# ESP32C_RF.net
KiCad netlist of a schematic drawn in Altium Designer
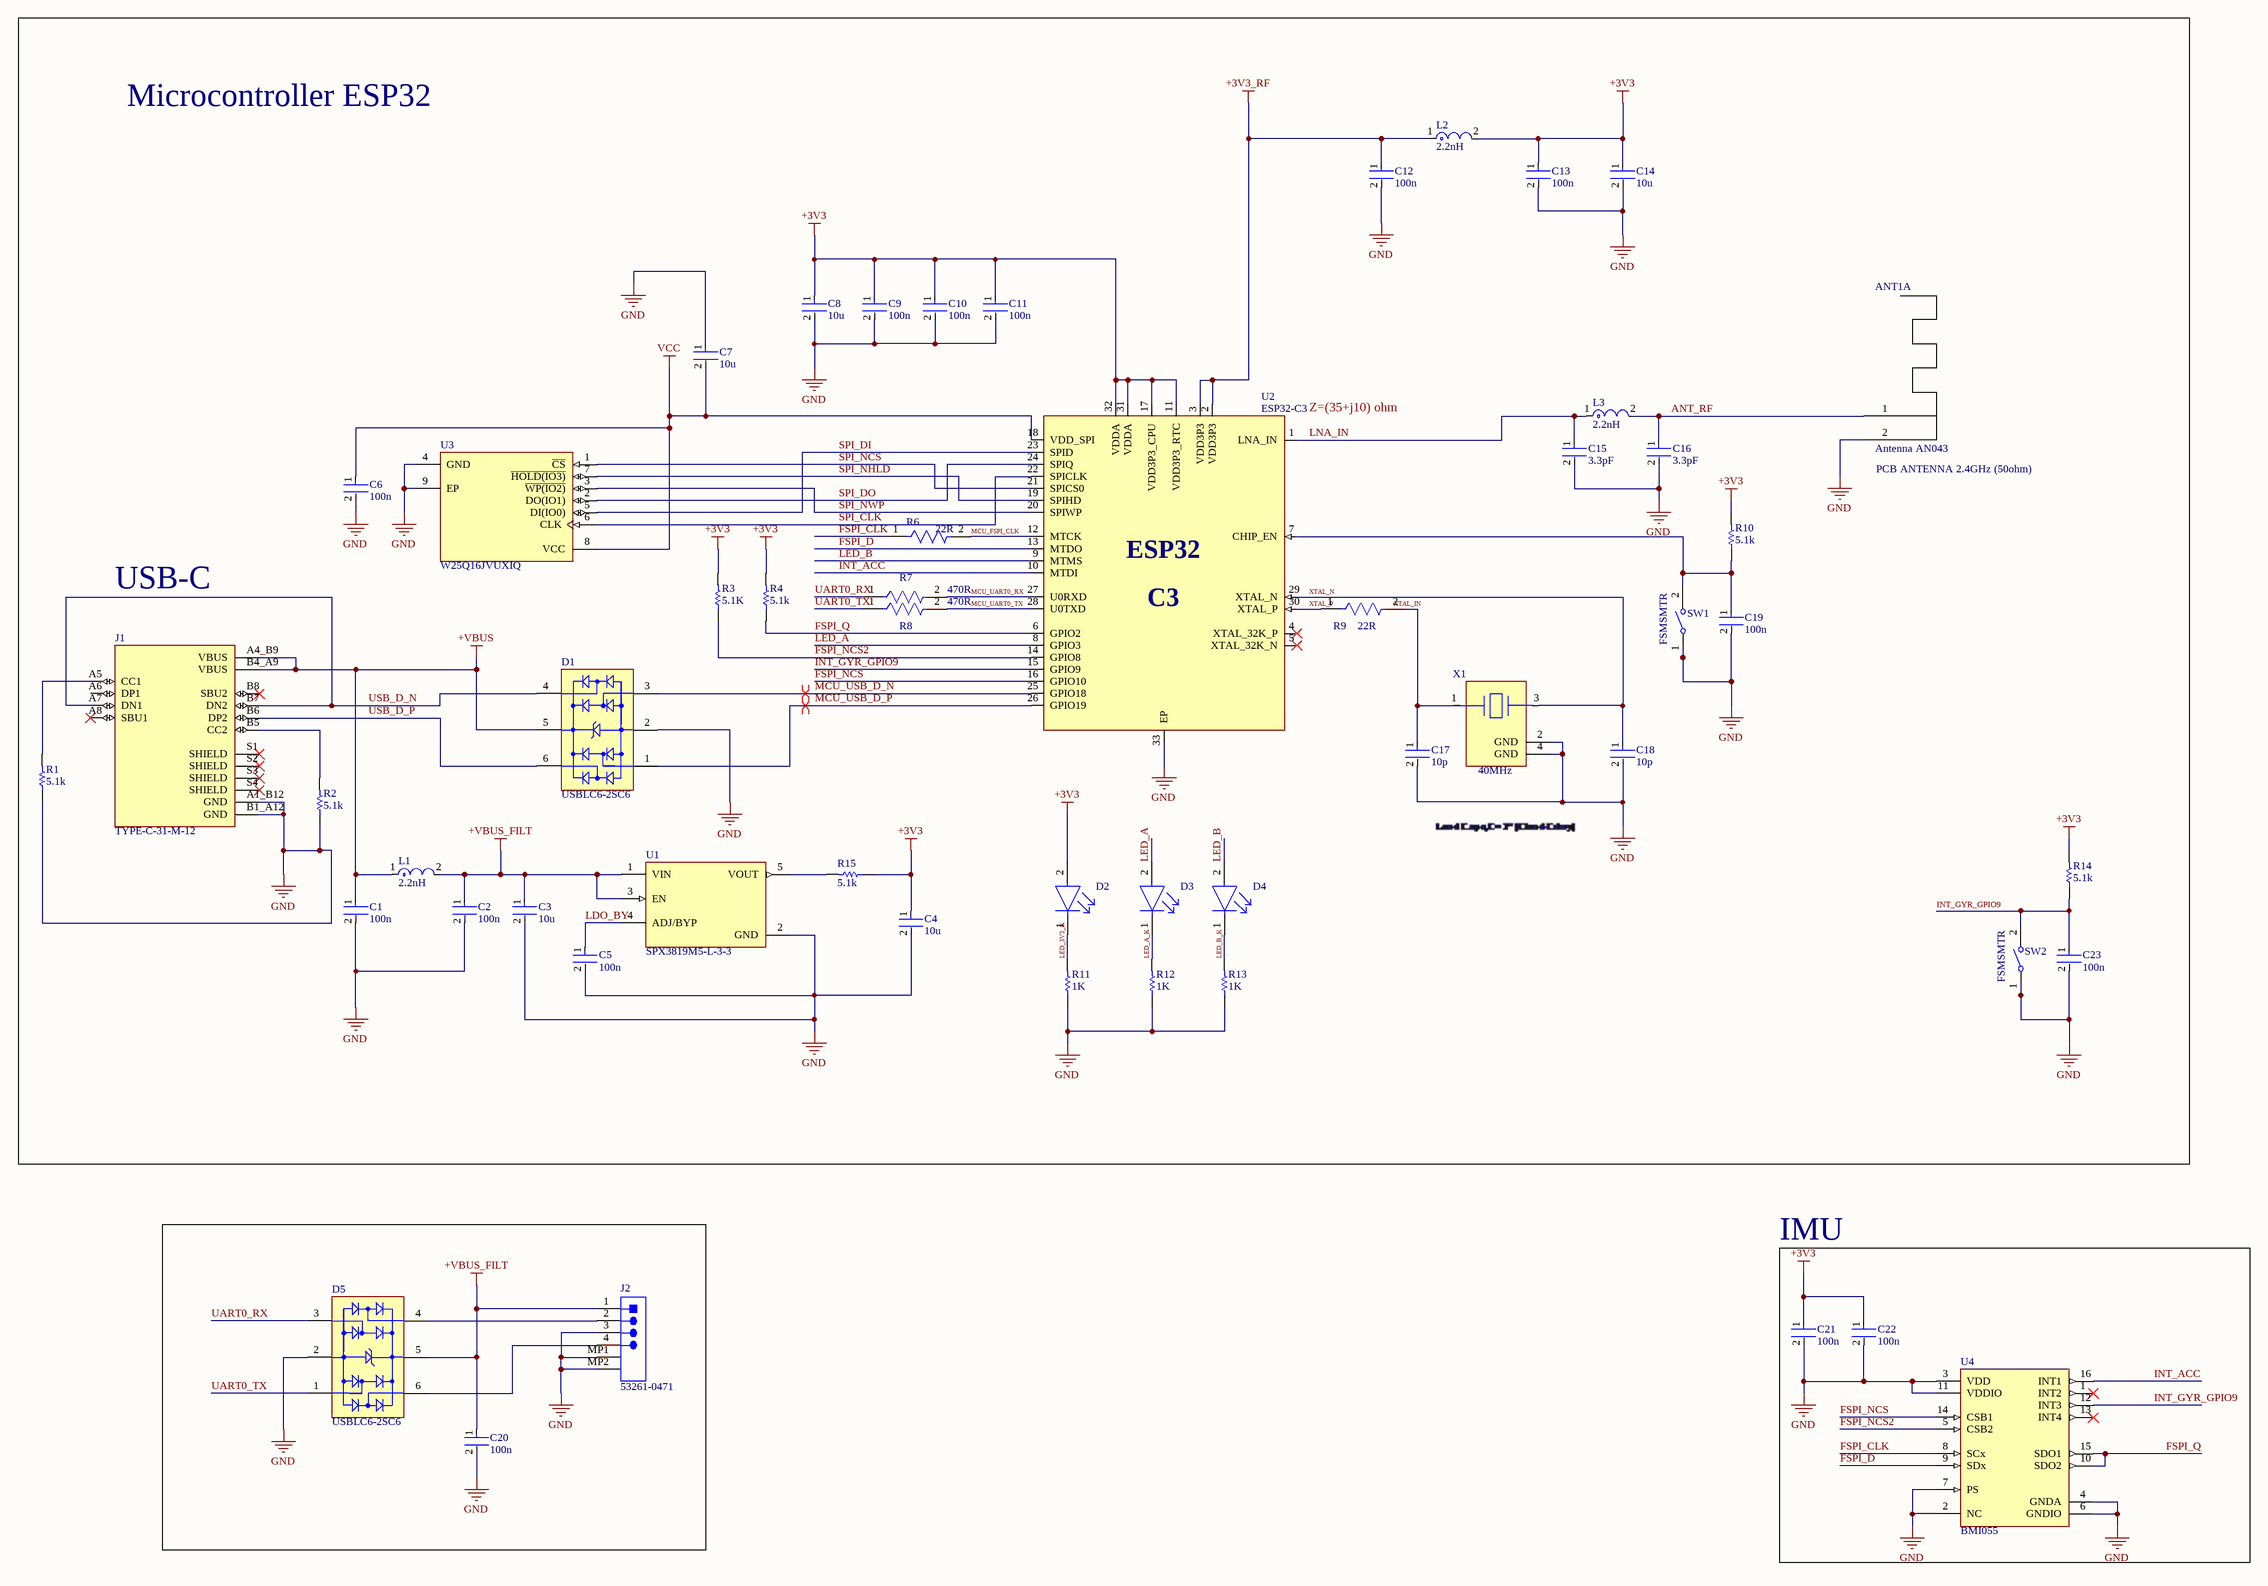
[diagram p0: ESP32C_RF.SchDoc]

(export (version "E")
  (design (tool "Eeschema 10.0.6"))
  (components
    (comp (ref "ANT1")
      (value "Antenna AN043")
      (footprint "Antenna_AN043")
      (libsource (lib "Library_Esp32C") (part "Antenna AN043"))
    )
    (comp (ref "C1")
      (value "100n")
      (footprint "FP-C0402-BB-MFG")
      (description "CAP CER 0.1UF 10V X5R 0402")
      (fields (field (name "MANUFACTURER") "Kemet") (field (name "TOLERANCE") "0.1"))
      (libsource (lib "Altium Content Vault") (part "b4654b650e69147ec39a6b967a45e02"))
    )
    (comp (ref "C2")
      (value "100n")
      (footprint "FP-C0402-BB-MFG")
      (description "CAP CER 0.1UF 10V X5R 0402")
      (fields (field (name "MANUFACTURER") "Kemet") (field (name "TOLERANCE") "0.1"))
      (libsource (lib "Altium Content Vault") (part "b4654b650e69147ec39a6b967a45e02"))
    )
    (comp (ref "C3")
      (value "10u")
      (footprint "FP-0603-L_1_6_0_15-W_0_81-MFG")
      (description "General Purpose Ceramic Capacitor, 0603, 100nF, 10%, X7R, 15%, 50V")
      (fields (field (name "TOLERANCE") "10%") (field (name "VOLTAGE") "50V"))
      (libsource (lib "Altium Content Vault") (part "02cd4be3c70576c341d710602a673aa"))
    )
    (comp (ref "C4")
      (value "10u")
      (footprint "FP-0603-L_1_6_0_15-W_0_81-MFG")
      (description "General Purpose Ceramic Capacitor, 0603, 100nF, 10%, X7R, 15%, 50V")
      (fields (field (name "TOLERANCE") "10%") (field (name "VOLTAGE") "50V"))
      (libsource (lib "Altium Content Vault") (part "02cd4be3c70576c341d710602a673aa"))
    )
    (comp (ref "C5")
      (value "100n")
      (footprint "FP-C0402-BB-MFG")
      (description "CAP CER 0.1UF 10V X5R 0402")
      (fields (field (name "MANUFACTURER") "Kemet") (field (name "TOLERANCE") "0.1"))
      (libsource (lib "Altium Content Vault") (part "b4654b650e69147ec39a6b967a45e02"))
    )
    (comp (ref "C6")
      (value "100n")
      (footprint "FP-C0402-BB-MFG")
      (description "CAP CER 0.1UF 10V X5R 0402")
      (fields (field (name "MANUFACTURER") "Kemet") (field (name "TOLERANCE") "0.1"))
      (libsource (lib "Altium Content Vault") (part "b4654b650e69147ec39a6b967a45e02"))
    )
    (comp (ref "C7")
      (value "10u")
      (footprint "FP-0603-L_1_6_0_15-W_0_81-MFG")
      (description "General Purpose Ceramic Capacitor, 0603, 100nF, 10%, X7R, 15%, 50V")
      (fields (field (name "TOLERANCE") "10%") (field (name "VOLTAGE") "50V"))
      (libsource (lib "Altium Content Vault") (part "02cd4be3c70576c341d710602a673aa"))
    )
    (comp (ref "C8")
      (value "10u")
      (footprint "FP-0603-L_1_6_0_15-W_0_81-MFG")
      (description "General Purpose Ceramic Capacitor, 0603, 100nF, 10%, X7R, 15%, 50V")
      (fields (field (name "TOLERANCE") "10%") (field (name "VOLTAGE") "50V"))
      (libsource (lib "Altium Content Vault") (part "02cd4be3c70576c341d710602a673aa"))
    )
    (comp (ref "C9")
      (value "100n")
      (footprint "FP-C0402-BB-MFG")
      (description "CAP CER 0.1UF 10V X5R 0402")
      (fields (field (name "MANUFACTURER") "Kemet") (field (name "TOLERANCE") "0.1"))
      (libsource (lib "Altium Content Vault") (part "b4654b650e69147ec39a6b967a45e02"))
    )
    (comp (ref "C10")
      (value "100n")
      (footprint "FP-C0402-BB-MFG")
      (description "CAP CER 0.1UF 10V X5R 0402")
      (fields (field (name "MANUFACTURER") "Kemet") (field (name "TOLERANCE") "0.1"))
      (libsource (lib "Altium Content Vault") (part "b4654b650e69147ec39a6b967a45e02"))
    )
    (comp (ref "C11")
      (value "100n")
      (footprint "FP-C0402-BB-MFG")
      (description "CAP CER 0.1UF 10V X5R 0402")
      (fields (field (name "MANUFACTURER") "Kemet") (field (name "TOLERANCE") "0.1"))
      (libsource (lib "Altium Content Vault") (part "b4654b650e69147ec39a6b967a45e02"))
    )
    (comp (ref "C12")
      (value "100n")
      (footprint "FP-C0402-BB-MFG")
      (description "CAP CER 0.1UF 10V X5R 0402")
      (fields (field (name "MANUFACTURER") "Kemet") (field (name "TOLERANCE") "0.1"))
      (libsource (lib "Altium Content Vault") (part "b4654b650e69147ec39a6b967a45e02"))
    )
    (comp (ref "C13")
      (value "100n")
      (footprint "FP-C0402-BB-MFG")
      (description "CAP CER 0.1UF 10V X5R 0402")
      (fields (field (name "MANUFACTURER") "Kemet") (field (name "TOLERANCE") "0.1"))
      (libsource (lib "Altium Content Vault") (part "b4654b650e69147ec39a6b967a45e02"))
    )
    (comp (ref "C14")
      (value "10u")
      (footprint "FP-0603-L_1_6_0_15-W_0_81-MFG")
      (description "General Purpose Ceramic Capacitor, 0603, 100nF, 10%, X7R, 15%, 50V")
      (fields (field (name "TOLERANCE") "10%") (field (name "VOLTAGE") "50V"))
      (libsource (lib "Altium Content Vault") (part "02cd4be3c70576c341d710602a673aa"))
    )
    (comp (ref "C15")
      (value "3.3pF")
      (footprint "FP-C0402-BB-MFG")
      (description "CAP CER 0.1UF 10V X5R 0402")
      (fields (field (name "MANUFACTURER") "Kemet") (field (name "TOLERANCE") "0.1"))
      (libsource (lib "Altium Content Vault") (part "b4654b650e69147ec39a6b967a45e02"))
    )
    (comp (ref "C16")
      (value "3.3pF")
      (footprint "FP-C0402-BB-MFG")
      (description "CAP CER 0.1UF 10V X5R 0402")
      (fields (field (name "MANUFACTURER") "Kemet") (field (name "TOLERANCE") "0.1"))
      (libsource (lib "Altium Content Vault") (part "b4654b650e69147ec39a6b967a45e02"))
    )
    (comp (ref "C17")
      (value "10p")
      (footprint "FP-C0402-BB-MFG")
      (description "CAP CER 0.1UF 10V X5R 0402")
      (fields (field (name "MANUFACTURER") "Kemet") (field (name "TOLERANCE") "0.1"))
      (libsource (lib "Altium Content Vault") (part "b4654b650e69147ec39a6b967a45e02"))
    )
    (comp (ref "C18")
      (value "10p")
      (footprint "FP-C0402-BB-MFG")
      (description "CAP CER 0.1UF 10V X5R 0402")
      (fields (field (name "MANUFACTURER") "Kemet") (field (name "TOLERANCE") "0.1"))
      (libsource (lib "Altium Content Vault") (part "b4654b650e69147ec39a6b967a45e02"))
    )
    (comp (ref "C19")
      (value "100n")
      (footprint "FP-C0402-BB-MFG")
      (description "CAP CER 0.1UF 10V X5R 0402")
      (fields (field (name "MANUFACTURER") "Kemet") (field (name "TOLERANCE") "0.1"))
      (libsource (lib "Altium Content Vault") (part "b4654b650e69147ec39a6b967a45e02"))
    )
    (comp (ref "C20")
      (value "100n")
      (footprint "FP-C0402-BB-MFG")
      (description "CAP CER 0.1UF 10V X5R 0402")
      (fields (field (name "MANUFACTURER") "Kemet") (field (name "TOLERANCE") "0.1"))
      (libsource (lib "Altium Content Vault") (part "b4654b650e69147ec39a6b967a45e02"))
    )
    (comp (ref "C21")
      (value "100n")
      (footprint "FP-C0402-BB-MFG")
      (description "CAP CER 0.1UF 10V X5R 0402")
      (fields (field (name "MANUFACTURER") "Kemet") (field (name "TOLERANCE") "0.1"))
      (libsource (lib "Altium Content Vault") (part "b4654b650e69147ec39a6b967a45e02"))
    )
    (comp (ref "C22")
      (value "100n")
      (footprint "FP-C0402-BB-MFG")
      (description "CAP CER 0.1UF 10V X5R 0402")
      (fields (field (name "MANUFACTURER") "Kemet") (field (name "TOLERANCE") "0.1"))
      (libsource (lib "Altium Content Vault") (part "b4654b650e69147ec39a6b967a45e02"))
    )
    (comp (ref "C23")
      (value "100n")
      (footprint "FP-C0402-BB-MFG")
      (description "CAP CER 0.1UF 10V X5R 0402")
      (fields (field (name "MANUFACTURER") "Kemet") (field (name "TOLERANCE") "0.1"))
      (libsource (lib "Altium Content Vault") (part "b4654b650e69147ec39a6b967a45e02"))
    )
    (comp (ref "D1")
      (value "USBLC6-2SC6")
      (footprint "STM-SOT23-6L_V")
      (description "Very low capacitance ESD protection, 3.5 pF, -40 to 125 degC, 6-Pin SOT23, RoHS, Tape and Reel")
      (fields (field (name "MANUFACTURER") "STMicroelectronics"))
      (libsource (lib "Altium Content Vault") (part "STM-USB_DVI_HDMIULC6-4SC6X-SOT23-6L"))
    )
    (comp (ref "D2")
      (value "LTST-C190KRKT")
      (footprint "FP-LTST-C190KRKT-MFG")
      (description "LED RED CLEAR CHIP SMD")
      (libsource (lib "Altium Content Vault") (part "8706943c75ba83719d021d2fdc84c58"))
    )
    (comp (ref "D3")
      (value "LTST-C190KRKT")
      (footprint "FP-LTST-C190KRKT-MFG")
      (description "LED RED CLEAR CHIP SMD")
      (libsource (lib "Altium Content Vault") (part "8706943c75ba83719d021d2fdc84c58"))
    )
    (comp (ref "D4")
      (value "LTST-C190KRKT")
      (footprint "FP-LTST-C190KRKT-MFG")
      (description "LED RED CLEAR CHIP SMD")
      (libsource (lib "Altium Content Vault") (part "8706943c75ba83719d021d2fdc84c58"))
    )
    (comp (ref "D5")
      (value "USBLC6-2SC6")
      (footprint "STM-SOT23-6L_V")
      (description "Very low capacitance ESD protection, 3.5 pF, -40 to 125 degC, 6-Pin SOT23, RoHS, Tape and Reel")
      (fields (field (name "MANUFACTURER") "STMicroelectronics"))
      (libsource (lib "Altium Content Vault") (part "STM-USB_DVI_HDMIULC6-4SC6X-SOT23-6L"))
    )
    (comp (ref "J1")
      (value "TYPE-C-31-M-12")
      (footprint "HRO_TYPE-C-31-M-12")
      (description "USB Connectors 24 Receptacle 1 8.94*7.3mm RoHS")
      (fields (field (name "MF") "HRO Electronics Co., Ltd."))
      (libsource (lib "Library_Esp32C") (part "TYPE-C-31-M-12"))
    )
    (comp (ref "J2")
      (value "53261-0471")
      (footprint "MOLEX-53261-0471_V")
      (description "Male Header, Pitch 1.25 mm, 1 x 4 Position, Height 3.4 mm, -40 to 85 degC, RoHS, Tape and Reel")
      (fields (field (name "MANUFACTURER") "Molex"))
      (libsource (lib "Altium Content Vault") (part "CN-1P-2M-R4_A"))
    )
    (comp (ref "L1")
      (value "2.2nH")
      (footprint "FP-LQG15HH_02-IPC_A")
      (description "Multilayer type RF Inductor 3.6nH ±0.3nH 0.13Ω 700mA 0402")
      (libsource (lib "Altium Content Vault") (part "4cc4b267dca4c8e51f7102f422741d8"))
    )
    (comp (ref "L2")
      (value "2.2nH")
      (footprint "FP-LQG15HH_02-IPC_A")
      (description "Multilayer type RF Inductor 3.6nH ±0.3nH 0.13Ω 700mA 0402")
      (libsource (lib "Altium Content Vault") (part "4cc4b267dca4c8e51f7102f422741d8"))
    )
    (comp (ref "L3")
      (value "2.2nH")
      (footprint "FP-LQG15HH_02-IPC_A")
      (description "Multilayer type RF Inductor 3.6nH ±0.3nH 0.13Ω 700mA 0402")
      (libsource (lib "Altium Content Vault") (part "4cc4b267dca4c8e51f7102f422741d8"))
    )
    (comp (ref "R1")
      (value "5.1k")
      (footprint "RESC1005X40X25LL05T05")
      (fields (field (name "MANUFACTURER") "Vishay Dale") (field (name "PART NUMBER") "CRCW040222R0FKED"))
      (libsource (lib "Altium Content Vault") (part "RES"))
    )
    (comp (ref "R2")
      (value "5.1k")
      (footprint "RESC1005X40X25LL05T05")
      (fields (field (name "MANUFACTURER") "Vishay Dale") (field (name "PART NUMBER") "CRCW040222R0FKED"))
      (libsource (lib "Altium Content Vault") (part "RES"))
    )
    (comp (ref "R3")
      (value "5.1K")
      (footprint "RESC1005X40X25LL05T05")
      (fields (field (name "MANUFACTURER") "Vishay Dale") (field (name "PART NUMBER") "CRCW040222R0FKED"))
      (libsource (lib "Altium Content Vault") (part "RES"))
    )
    (comp (ref "R4")
      (value "5.1k")
      (footprint "RESC1005X40X25LL05T05")
      (fields (field (name "MANUFACTURER") "Vishay Dale") (field (name "PART NUMBER") "CRCW040222R0FKED"))
      (libsource (lib "Altium Content Vault") (part "RES"))
    )
    (comp (ref "R6")
      (value "22R")
      (footprint "FP-CRCW0402-e3-IPC_C")
      (description "RES Thick Film, 100Ω, 1%, 0.063W, 100ppm/°C, 0402")
      (fields (field (name "TOLERANCE") "1%"))
      (libsource (lib "Altium Content Vault") (part "1029c3af85768c4190bb7ad29bc67b5"))
    )
    (comp (ref "R7")
      (value "470R")
      (footprint "FP-ERJ2RK-IPC_C")
      (description "RES SMD 470 OHM 1% 1/10W 0402")
      (fields (field (name "TOLERANCE") "1%"))
      (libsource (lib "Altium Content Vault") (part "8db39607336c341a927600551d01821"))
    )
    (comp (ref "R8")
      (value "470R")
      (footprint "FP-ERJ2RK-IPC_C")
      (description "RES SMD 470 OHM 1% 1/10W 0402")
      (fields (field (name "TOLERANCE") "1%"))
      (libsource (lib "Altium Content Vault") (part "8db39607336c341a927600551d01821"))
    )
    (comp (ref "R9")
      (value "22R")
      (footprint "FP-CRCW0402-e3-IPC_C")
      (description "RES Thick Film, 100Ω, 1%, 0.063W, 100ppm/°C, 0402")
      (fields (field (name "TOLERANCE") "1%"))
      (libsource (lib "Altium Content Vault") (part "1029c3af85768c4190bb7ad29bc67b5"))
    )
    (comp (ref "R10")
      (value "5.1k")
      (footprint "RESC1005X40X25LL05T05")
      (fields (field (name "MANUFACTURER") "Vishay Dale") (field (name "PART NUMBER") "CRCW040222R0FKED"))
      (libsource (lib "Altium Content Vault") (part "RES"))
    )
    (comp (ref "R11")
      (value "1K")
      (footprint "RESC1005X40X25LL05T05")
      (fields (field (name "MANUFACTURER") "Vishay Dale") (field (name "PART NUMBER") "CRCW040222R0FKED"))
      (libsource (lib "Altium Content Vault") (part "RES"))
    )
    (comp (ref "R12")
      (value "1K")
      (footprint "RESC1005X40X25LL05T05")
      (fields (field (name "MANUFACTURER") "Vishay Dale") (field (name "PART NUMBER") "CRCW040222R0FKED"))
      (libsource (lib "Altium Content Vault") (part "RES"))
    )
    (comp (ref "R13")
      (value "1K")
      (footprint "RESC1005X40X25LL05T05")
      (fields (field (name "MANUFACTURER") "Vishay Dale") (field (name "PART NUMBER") "CRCW040222R0FKED"))
      (libsource (lib "Altium Content Vault") (part "RES"))
    )
    (comp (ref "R14")
      (value "5.1k")
      (footprint "RESC1005X40X25LL05T05")
      (fields (field (name "MANUFACTURER") "Vishay Dale") (field (name "PART NUMBER") "CRCW040222R0FKED"))
      (libsource (lib "Altium Content Vault") (part "RES"))
    )
    (comp (ref "R15")
      (value "5.1k")
      (footprint "RESC1005X40X25LL05T05")
      (fields (field (name "MANUFACTURER") "Vishay Dale") (field (name "PART NUMBER") "CRCW040222R0FKED"))
      (libsource (lib "Altium Content Vault") (part "RES"))
    )
    (comp (ref "SW1")
      (value "FSMSMTR")
      (footprint "TECO-FSMSMTR_V")
      (description "FSMSM Push Button Switch, 50 mA, -35 to 85 degC, 2-Pin SMD, RoHS, Tape and Reel")
      (fields (field (name "MANUFACTURER") "TE Connectivity"))
      (libsource (lib "Altium Content Vault") (part "SW-SPST-2_C"))
    )
    (comp (ref "SW2")
      (value "FSMSMTR")
      (footprint "TECO-FSMSMTR_V")
      (description "FSMSM Push Button Switch, 50 mA, -35 to 85 degC, 2-Pin SMD, RoHS, Tape and Reel")
      (fields (field (name "MANUFACTURER") "TE Connectivity"))
      (libsource (lib "Altium Content Vault") (part "SW-SPST-2_C"))
    )
    (comp (ref "U1")
      (value "SPX3819M5-L-3-3")
      (footprint "SOT95P280X145-5N")
      (description "Linear Voltage Regulator IC Positive Fixed 1 Output 500mA SOT-23-5")
      (fields (field (name "MF") "MaxLinear, Inc.") (field (name "MP") "SPX3819M5-L-3-3/TR"))
      (libsource (lib "Library_Esp32C") (part "SPX3819M5-L-3-3"))
    )
    (comp (ref "U2")
      (value "ESP32-C3")
      (footprint "QFN50P500X500X90-33N-D")
      (fields (field (name "MANUFACTURER") "Espressif"))
      (libsource (lib "Library_Esp32C") (part "ESP32-C3"))
    )
    (comp (ref "U3")
      (value "W25Q16JVUXIQ")
      (footprint "FP-UX-MFG")
      (description "IC FLASH 16MBIT SPI/QUAD 8USON")
      (libsource (lib "Altium Content Vault") (part "ef7e6bbff5b18f94b0c5acc221a373e"))
    )
    (comp (ref "U4")
      (value "BMI055")
      (footprint "FP-BMI055-MFG")
      (description "IMU ACCEL/GYRO I2C/SPI 16LGA")
      (libsource (lib "Altium Content Vault") (part "27928433b13d6d742e94b461c0d61b2"))
    )
    (comp (ref "X1")
      (value "40MHz")
      (footprint "FP-NX2520SA-MFG")
      (description "CRYSTAL 16.0000MHZ 8PF SMD")
      (libsource (lib "Altium Content Vault") (part "07cd68334262f73c450eeb7a763f26b"))
    )
  )
  (nets
    (net (code "1") (name "+3V3") (class "Default")
      (node (ref "C10") (pin "1") (pinfunction "1_1") (pintype "passive"))
      (node (ref "C11") (pin "1") (pinfunction "1_1") (pintype "passive"))
      (node (ref "C13") (pin "1") (pinfunction "1_1") (pintype "passive"))
      (node (ref "C14") (pin "1") (pinfunction "1_1") (pintype "passive"))
      (node (ref "C21") (pin "1") (pinfunction "1_1") (pintype "passive"))
      (node (ref "C22") (pin "1") (pinfunction "1_1") (pintype "passive"))
      (node (ref "C4") (pin "1") (pinfunction "1_1") (pintype "passive"))
      (node (ref "C8") (pin "1") (pinfunction "1_1") (pintype "passive"))
      (node (ref "C9") (pin "1") (pinfunction "1_1") (pintype "passive"))
      (node (ref "D2") (pin "2") (pinfunction "A_2") (pintype "passive"))
      (node (ref "L2") (pin "2") (pinfunction "2_2") (pintype "passive"))
      (node (ref "R10") (pin "2") (pinfunction "2_2") (pintype "passive"))
      (node (ref "R14") (pin "2") (pinfunction "2_2") (pintype "passive"))
      (node (ref "R15") (pin "1") (pinfunction "1_1") (pintype "passive"))
      (node (ref "R3") (pin "2") (pinfunction "2_2") (pintype "passive"))
      (node (ref "R4") (pin "2") (pinfunction "2_2") (pintype "passive"))
      (node (ref "U2") (pin "11") (pinfunction "VDD3P3_RTC_11") (pintype "power_in"))
      (node (ref "U2") (pin "17") (pinfunction "VDD3P3_CPU_17") (pintype "power_in"))
      (node (ref "U2") (pin "31") (pinfunction "VDDA_31") (pintype "power_in"))
      (node (ref "U2") (pin "32") (pinfunction "VDDA_32") (pintype "power_in"))
    )
    (net (code "2") (name "+3V3_RF") (class "Default")
      (node (ref "C12") (pin "1") (pinfunction "1_1") (pintype "passive"))
      (node (ref "L2") (pin "1") (pinfunction "1_1") (pintype "passive"))
      (node (ref "U2") (pin "2") (pinfunction "VDD3P3_2") (pintype "power_in"))
      (node (ref "U2") (pin "3") (pinfunction "VDD3P3_3") (pintype "power_in"))
    )
    (net (code "3") (name "+VBUS") (class "Default")
      (node (ref "C1") (pin "1") (pinfunction "1_1") (pintype "passive"))
      (node (ref "D1") (pin "5") (pinfunction "VBUS_5") (pintype "passive"))
      (node (ref "J1") (pin "A4_B9") (pinfunction "VBUS_A4_B9") (pintype "power_in"))
      (node (ref "J1") (pin "B4_A9") (pinfunction "VBUS_B4_A9") (pintype "power_in"))
      (node (ref "L1") (pin "1") (pinfunction "1_1") (pintype "passive"))
    )
    (net (code "4") (name "+VBUS_FILT") (class "Default")
      (node (ref "C2") (pin "1") (pinfunction "1_1") (pintype "passive"))
      (node (ref "C20") (pin "1") (pinfunction "1_1") (pintype "passive"))
      (node (ref "C3") (pin "1") (pinfunction "1_1") (pintype "passive"))
      (node (ref "D5") (pin "5") (pinfunction "VBUS_5") (pintype "passive"))
      (node (ref "J2") (pin "1") (pinfunction "1_1") (pintype "passive"))
      (node (ref "L1") (pin "2") (pinfunction "2_2") (pintype "passive"))
      (node (ref "U1") (pin "1") (pinfunction "VIN_1") (pintype "power_in"))
      (node (ref "U1") (pin "3") (pinfunction "EN_3") (pintype "input"))
    )
    (net (code "5") (name "/ANT_RF") (class "Default")
      (node (ref "ANT1") (pin "1") (pinfunction "Antenna_1") (pintype "passive"))
      (node (ref "C16") (pin "1") (pinfunction "1_1") (pintype "passive"))
      (node (ref "L3") (pin "2") (pinfunction "2_2") (pintype "passive"))
    )
    (net (code "6") (name "/FSPI_CLK") (class "Default")
      (node (ref "R6") (pin "1") (pinfunction "1_1") (pintype "passive"))
      (node (ref "U4") (pin "8") (pinfunction "SCx_8") (pintype "input"))
    )
    (net (code "7") (name "/FSPI_D") (class "Default")
      (node (ref "U2") (pin "13") (pinfunction "MTDO_13") (pintype "bidirectional"))
      (node (ref "U4") (pin "9") (pinfunction "SDx_9") (pintype "input"))
    )
    (net (code "8") (name "/FSPI_NCS") (class "Default")
      (node (ref "U2") (pin "16") (pinfunction "GPIO10_16") (pintype "bidirectional"))
      (node (ref "U4") (pin "14") (pinfunction "CSB1_14") (pintype "input"))
    )
    (net (code "9") (name "/FSPI_NCS2") (class "Default")
      (node (ref "R3") (pin "1") (pinfunction "1_1") (pintype "passive"))
      (node (ref "U2") (pin "14") (pinfunction "GPIO8_14") (pintype "bidirectional"))
      (node (ref "U4") (pin "5") (pinfunction "CSB2_5") (pintype "input"))
    )
    (net (code "10") (name "/FSPI_Q") (class "Default")
      (node (ref "R4") (pin "1") (pinfunction "1_1") (pintype "passive"))
      (node (ref "U2") (pin "6") (pinfunction "GPIO2_6") (pintype "bidirectional"))
      (node (ref "U4") (pin "10") (pinfunction "SDO2_10") (pintype "output"))
      (node (ref "U4") (pin "15") (pinfunction "SDO1_15") (pintype "output"))
    )
    (net (code "11") (name "/INT_ACC") (class "Default")
      (node (ref "U2") (pin "10") (pinfunction "MTDI_10") (pintype "bidirectional"))
      (node (ref "U4") (pin "16") (pinfunction "INT1_16") (pintype "output"))
    )
    (net (code "12") (name "/INT_GYR_GPIO9") (class "Default")
      (node (ref "C23") (pin "1") (pinfunction "1_1") (pintype "passive"))
      (node (ref "R14") (pin "1") (pinfunction "1_1") (pintype "passive"))
      (node (ref "SW2") (pin "2") (pinfunction "2_2") (pintype "passive"))
      (node (ref "U2") (pin "15") (pinfunction "GPIO9_15") (pintype "bidirectional"))
      (node (ref "U4") (pin "12") (pinfunction "INT3_12") (pintype "output"))
    )
    (net (code "13") (name "/LDO_BY") (class "Default")
      (node (ref "C5") (pin "1") (pinfunction "1_1") (pintype "passive"))
      (node (ref "U1") (pin "4") (pinfunction "ADJ/BYP_4") (pintype "passive"))
    )
    (net (code "14") (name "/LED_3V3_K") (class "Default")
      (node (ref "D2") (pin "1") (pinfunction "C_1") (pintype "passive"))
      (node (ref "R11") (pin "2") (pinfunction "2_2") (pintype "passive"))
    )
    (net (code "15") (name "/LED_A") (class "Default")
      (node (ref "D3") (pin "2") (pinfunction "A_2") (pintype "passive"))
      (node (ref "U2") (pin "8") (pinfunction "GPIO3_8") (pintype "bidirectional"))
    )
    (net (code "16") (name "/LED_A_K") (class "Default")
      (node (ref "D3") (pin "1") (pinfunction "C_1") (pintype "passive"))
      (node (ref "R12") (pin "2") (pinfunction "2_2") (pintype "passive"))
    )
    (net (code "17") (name "/LED_B") (class "Default")
      (node (ref "D4") (pin "2") (pinfunction "A_2") (pintype "passive"))
      (node (ref "U2") (pin "9") (pinfunction "MTMS_9") (pintype "bidirectional"))
    )
    (net (code "18") (name "/LED_B_K") (class "Default")
      (node (ref "D4") (pin "1") (pinfunction "C_1") (pintype "passive"))
      (node (ref "R13") (pin "2") (pinfunction "2_2") (pintype "passive"))
    )
    (net (code "19") (name "/LNA_IN") (class "Default")
      (node (ref "C15") (pin "1") (pinfunction "1_1") (pintype "passive"))
      (node (ref "L3") (pin "1") (pinfunction "1_1") (pintype "passive"))
      (node (ref "U2") (pin "1") (pinfunction "LNA_IN_1") (pintype "bidirectional"))
    )
    (net (code "20") (name "/MCU_FSPI_CLK") (class "Default")
      (node (ref "R6") (pin "2") (pinfunction "2_2") (pintype "passive"))
      (node (ref "U2") (pin "12") (pinfunction "MTCK_12") (pintype "bidirectional"))
    )
    (net (code "21") (name "/MCU_UART0_RX") (class "Default")
      (node (ref "R7") (pin "2") (pinfunction "2_2") (pintype "passive"))
      (node (ref "U2") (pin "27") (pinfunction "U0RXD_27") (pintype "bidirectional"))
    )
    (net (code "22") (name "/MCU_UART0_TX") (class "Default")
      (node (ref "R8") (pin "2") (pinfunction "2_2") (pintype "passive"))
      (node (ref "U2") (pin "28") (pinfunction "U0TXD_28") (pintype "bidirectional"))
    )
    (net (code "23") (name "/MCU_USB_D_N") (class "Default")
      (node (ref "D1") (pin "3") (pinfunction "I/O_2_3") (pintype "passive"))
      (node (ref "U2") (pin "25") (pinfunction "GPIO18_25") (pintype "bidirectional"))
    )
    (net (code "24") (name "/MCU_USB_D_P") (class "Default")
      (node (ref "D1") (pin "1") (pinfunction "I/O_1_1") (pintype "passive"))
      (node (ref "U2") (pin "26") (pinfunction "GPIO19_26") (pintype "bidirectional"))
    )
    (net (code "25") (name "/SPI_CLK") (class "Default")
      (node (ref "U2") (pin "22") (pinfunction "SPICLK_22") (pintype "bidirectional"))
      (node (ref "U3") (pin "6") (pinfunction "CLK_6") (pintype "input"))
    )
    (net (code "26") (name "/SPI_DI") (class "Default")
      (node (ref "U2") (pin "23") (pinfunction "SPID_23") (pintype "bidirectional"))
      (node (ref "U3") (pin "5") (pinfunction "DI(IO0)_5") (pintype "bidirectional"))
    )
    (net (code "27") (name "/SPI_DO") (class "Default")
      (node (ref "U2") (pin "24") (pinfunction "SPIQ_24") (pintype "bidirectional"))
      (node (ref "U3") (pin "2") (pinfunction "DO(IO1)_2") (pintype "bidirectional"))
    )
    (net (code "28") (name "/SPI_NCS") (class "Default")
      (node (ref "U2") (pin "21") (pinfunction "SPICS0_21") (pintype "bidirectional"))
      (node (ref "U3") (pin "1") (pinfunction "~{CS}_1") (pintype "input"))
    )
    (net (code "29") (name "/SPI_NHLD") (class "Default")
      (node (ref "U2") (pin "19") (pinfunction "SPIHD_19") (pintype "bidirectional"))
      (node (ref "U3") (pin "7") (pinfunction "~{HOLD(IO3)}_7") (pintype "bidirectional"))
    )
    (net (code "30") (name "/SPI_NWP") (class "Default")
      (node (ref "U2") (pin "20") (pinfunction "SPIWP_20") (pintype "bidirectional"))
      (node (ref "U3") (pin "3") (pinfunction "~{WP(IO2)}_3") (pintype "bidirectional"))
    )
    (net (code "31") (name "/UART0_RX") (class "Default")
      (node (ref "D5") (pin "3") (pinfunction "I/O_2_3") (pintype "passive"))
      (node (ref "R7") (pin "1") (pinfunction "1_1") (pintype "passive"))
    )
    (net (code "32") (name "/UART0_TX") (class "Default")
      (node (ref "D5") (pin "1") (pinfunction "I/O_1_1") (pintype "passive"))
      (node (ref "R8") (pin "1") (pinfunction "1_1") (pintype "passive"))
    )
    (net (code "33") (name "/USB_D_N") (class "Default")
      (node (ref "D1") (pin "4") (pinfunction "I/O_3_4") (pintype "passive"))
      (node (ref "J1") (pin "A7") (pinfunction "DN1_A7") (pintype "bidirectional"))
      (node (ref "J1") (pin "B7") (pinfunction "DN2_B7") (pintype "bidirectional"))
    )
    (net (code "34") (name "/USB_D_P") (class "Default")
      (node (ref "D1") (pin "6") (pinfunction "I/O_4_6") (pintype "passive"))
      (node (ref "J1") (pin "B6") (pinfunction "DP2_B6") (pintype "bidirectional"))
    )
    (net (code "36") (name "/XTAL_N") (class "Default")
      (node (ref "C18") (pin "1") (pinfunction "1_1") (pintype "passive"))
      (node (ref "U2") (pin "29") (pinfunction "XTAL_N_29") (pintype "input"))
      (node (ref "X1") (pin "3") (pinfunction "3_3") (pintype "passive"))
    )
    (net (code "37") (name "/XTAL_P") (class "Default")
      (node (ref "R9") (pin "1") (pinfunction "1_1") (pintype "passive"))
      (node (ref "U2") (pin "30") (pinfunction "XTAL_P_30") (pintype "input"))
    )
    (net (code "38") (name "GND") (class "Default")
      (node (ref "ANT1") (pin "2") (pinfunction "GND_2") (pintype "passive"))
      (node (ref "C1") (pin "2") (pinfunction "2_2") (pintype "passive"))
      (node (ref "C10") (pin "2") (pinfunction "2_2") (pintype "passive"))
      (node (ref "C11") (pin "2") (pinfunction "2_2") (pintype "passive"))
      (node (ref "C12") (pin "2") (pinfunction "2_2") (pintype "passive"))
      (node (ref "C13") (pin "2") (pinfunction "2_2") (pintype "passive"))
      (node (ref "C14") (pin "2") (pinfunction "2_2") (pintype "passive"))
      (node (ref "C15") (pin "2") (pinfunction "2_2") (pintype "passive"))
      (node (ref "C16") (pin "2") (pinfunction "2_2") (pintype "passive"))
      (node (ref "C17") (pin "2") (pinfunction "2_2") (pintype "passive"))
      (node (ref "C18") (pin "2") (pinfunction "2_2") (pintype "passive"))
      (node (ref "C19") (pin "2") (pinfunction "2_2") (pintype "passive"))
      (node (ref "C2") (pin "2") (pinfunction "2_2") (pintype "passive"))
      (node (ref "C20") (pin "2") (pinfunction "2_2") (pintype "passive"))
      (node (ref "C21") (pin "2") (pinfunction "2_2") (pintype "passive"))
      (node (ref "C22") (pin "2") (pinfunction "2_2") (pintype "passive"))
      (node (ref "C23") (pin "2") (pinfunction "2_2") (pintype "passive"))
      (node (ref "C3") (pin "2") (pinfunction "2_2") (pintype "passive"))
      (node (ref "C4") (pin "2") (pinfunction "2_2") (pintype "passive"))
      (node (ref "C5") (pin "2") (pinfunction "2_2") (pintype "passive"))
      (node (ref "C6") (pin "2") (pinfunction "2_2") (pintype "passive"))
      (node (ref "C7") (pin "1") (pinfunction "1_1") (pintype "passive"))
      (node (ref "C8") (pin "2") (pinfunction "2_2") (pintype "passive"))
      (node (ref "C9") (pin "2") (pinfunction "2_2") (pintype "passive"))
      (node (ref "D1") (pin "2") (pinfunction "GND_2") (pintype "passive"))
      (node (ref "D5") (pin "2") (pinfunction "GND_2") (pintype "passive"))
      (node (ref "J1") (pin "A1_B12") (pinfunction "GND_A1_B12") (pintype "power_in"))
      (node (ref "J1") (pin "B1_A12") (pinfunction "GND_B1_A12") (pintype "power_in"))
      (node (ref "J2") (pin "3") (pinfunction "3_3") (pintype "passive"))
      (node (ref "J2") (pin "MP1") (pinfunction "MP1_MP1") (pintype "passive"))
      (node (ref "J2") (pin "MP2") (pinfunction "MP2_MP2") (pintype "passive"))
      (node (ref "R1") (pin "1") (pinfunction "1_1") (pintype "passive"))
      (node (ref "R11") (pin "1") (pinfunction "1_1") (pintype "passive"))
      (node (ref "R12") (pin "1") (pinfunction "1_1") (pintype "passive"))
      (node (ref "R13") (pin "1") (pinfunction "1_1") (pintype "passive"))
      (node (ref "R2") (pin "1") (pinfunction "1_1") (pintype "passive"))
      (node (ref "SW1") (pin "1") (pinfunction "1_1") (pintype "passive"))
      (node (ref "SW2") (pin "1") (pinfunction "1_1") (pintype "passive"))
      (node (ref "U1") (pin "2") (pinfunction "GND_2") (pintype "passive"))
      (node (ref "U2") (pin "33") (pinfunction "EP_33") (pintype "power_in"))
      (node (ref "U3") (pin "4") (pinfunction "GND_4") (pintype "power_in"))
      (node (ref "U3") (pin "9") (pinfunction "EP_9") (pintype "passive"))
      (node (ref "U4") (pin "11") (pinfunction "VDDIO_11") (pintype "power_in"))
      (node (ref "U4") (pin "2") (pinfunction "NC_2") (pintype "passive"))
      (node (ref "U4") (pin "3") (pinfunction "VDD_3") (pintype "power_in"))
      (node (ref "U4") (pin "4") (pinfunction "GNDA_4") (pintype "power_in"))
      (node (ref "U4") (pin "6") (pinfunction "GNDIO_6") (pintype "power_in"))
      (node (ref "U4") (pin "7") (pinfunction "PS_7") (pintype "input"))
      (node (ref "X1") (pin "2") (pinfunction "GND_2") (pintype "power_in"))
      (node (ref "X1") (pin "4") (pinfunction "GND_4") (pintype "power_in"))
    )
    (net (code "39") (name "Net-(C17-Pad1)") (class "Default")
      (node (ref "C17") (pin "1") (pinfunction "1_1") (pintype "passive"))
      (node (ref "R9") (pin "2") (pinfunction "2_2") (pintype "passive"))
      (node (ref "X1") (pin "1") (pinfunction "1_1") (pintype "passive"))
    )
    (net (code "40") (name "Net-(D5-I{slash}O_3)") (class "Default")
      (node (ref "D5") (pin "4") (pinfunction "I/O_3_4") (pintype "passive"))
      (node (ref "J2") (pin "2") (pinfunction "2_2") (pintype "passive"))
    )
    (net (code "41") (name "Net-(D5-I{slash}O_4)") (class "Default")
      (node (ref "D5") (pin "6") (pinfunction "I/O_4_6") (pintype "passive"))
      (node (ref "J2") (pin "4") (pinfunction "4_4") (pintype "passive"))
    )
    (net (code "42") (name "Net-(J1-CC1)") (class "Default")
      (node (ref "J1") (pin "A5") (pinfunction "CC1_A5") (pintype "bidirectional"))
      (node (ref "R1") (pin "2") (pinfunction "2_2") (pintype "passive"))
    )
    (net (code "43") (name "Net-(J1-CC2)") (class "Default")
      (node (ref "J1") (pin "B5") (pinfunction "CC2_B5") (pintype "bidirectional"))
      (node (ref "R2") (pin "2") (pinfunction "2_2") (pintype "passive"))
    )
    (net (code "44") (name "Net-(U1-VOUT)") (class "Default")
      (node (ref "R15") (pin "2") (pinfunction "2_2") (pintype "passive"))
      (node (ref "U1") (pin "5") (pinfunction "VOUT_5") (pintype "output"))
    )
    (net (code "45") (name "Net-(U2-CHIP_EN)") (class "Default")
      (node (ref "C19") (pin "1") (pinfunction "1_1") (pintype "passive"))
      (node (ref "R10") (pin "1") (pinfunction "1_1") (pintype "passive"))
      (node (ref "SW1") (pin "2") (pinfunction "2_2") (pintype "passive"))
      (node (ref "U2") (pin "7") (pinfunction "CHIP_EN_7") (pintype "input"))
    )
    (net (code "46") (name "VCC") (class "Default")
      (node (ref "C6") (pin "1") (pinfunction "1_1") (pintype "passive"))
      (node (ref "C7") (pin "2") (pinfunction "2_2") (pintype "passive"))
      (node (ref "U2") (pin "18") (pinfunction "VDD_SPI_18") (pintype "power_in"))
      (node (ref "U3") (pin "8") (pinfunction "VCC_8") (pintype "power_in"))
    )
    (net (code "47") (name "unconnected-(J1-DP1-PadA6)") (class "Default")
      (node (ref "J1") (pin "A6") (pinfunction "DP1_A6") (pintype "bidirectional"))
    )
    (net (code "48") (name "unconnected-(J1-SBU1-PadA8)") (class "Default")
      (node (ref "J1") (pin "A8") (pinfunction "SBU1_A8") (pintype "bidirectional+no_connect"))
    )
    (net (code "49") (name "unconnected-(J1-SBU2-PadB8)") (class "Default")
      (node (ref "J1") (pin "B8") (pinfunction "SBU2_B8") (pintype "bidirectional+no_connect"))
    )
    (net (code "50") (name "unconnected-(J1-SHIELD-PadS1)") (class "Default")
      (node (ref "J1") (pin "S1") (pinfunction "SHIELD_S1") (pintype "passive+no_connect"))
    )
    (net (code "51") (name "unconnected-(J1-SHIELD-PadS2)") (class "Default")
      (node (ref "J1") (pin "S2") (pinfunction "SHIELD_S2") (pintype "passive+no_connect"))
    )
    (net (code "52") (name "unconnected-(J1-SHIELD-PadS3)") (class "Default")
      (node (ref "J1") (pin "S3") (pinfunction "SHIELD_S3") (pintype "passive+no_connect"))
    )
    (net (code "53") (name "unconnected-(J1-SHIELD-PadS4)") (class "Default")
      (node (ref "J1") (pin "S4") (pinfunction "SHIELD_S4") (pintype "passive+no_connect"))
    )
    (net (code "54") (name "unconnected-(U2-XTAL_32K_N-Pad5)") (class "Default")
      (node (ref "U2") (pin "5") (pinfunction "XTAL_32K_N_5") (pintype "bidirectional+no_connect"))
    )
    (net (code "55") (name "unconnected-(U2-XTAL_32K_P-Pad4)") (class "Default")
      (node (ref "U2") (pin "4") (pinfunction "XTAL_32K_P_4") (pintype "bidirectional+no_connect"))
    )
    (net (code "56") (name "unconnected-(U4-INT2-Pad1)") (class "Default")
      (node (ref "U4") (pin "1") (pinfunction "INT2_1") (pintype "output+no_connect"))
    )
    (net (code "57") (name "unconnected-(U4-INT4-Pad13)") (class "Default")
      (node (ref "U4") (pin "13") (pinfunction "INT4_13") (pintype "output+no_connect"))
    )
  )
)
